# CTR_Connectors.net
KiCad netlist of a schematic drawn in Altium Designer
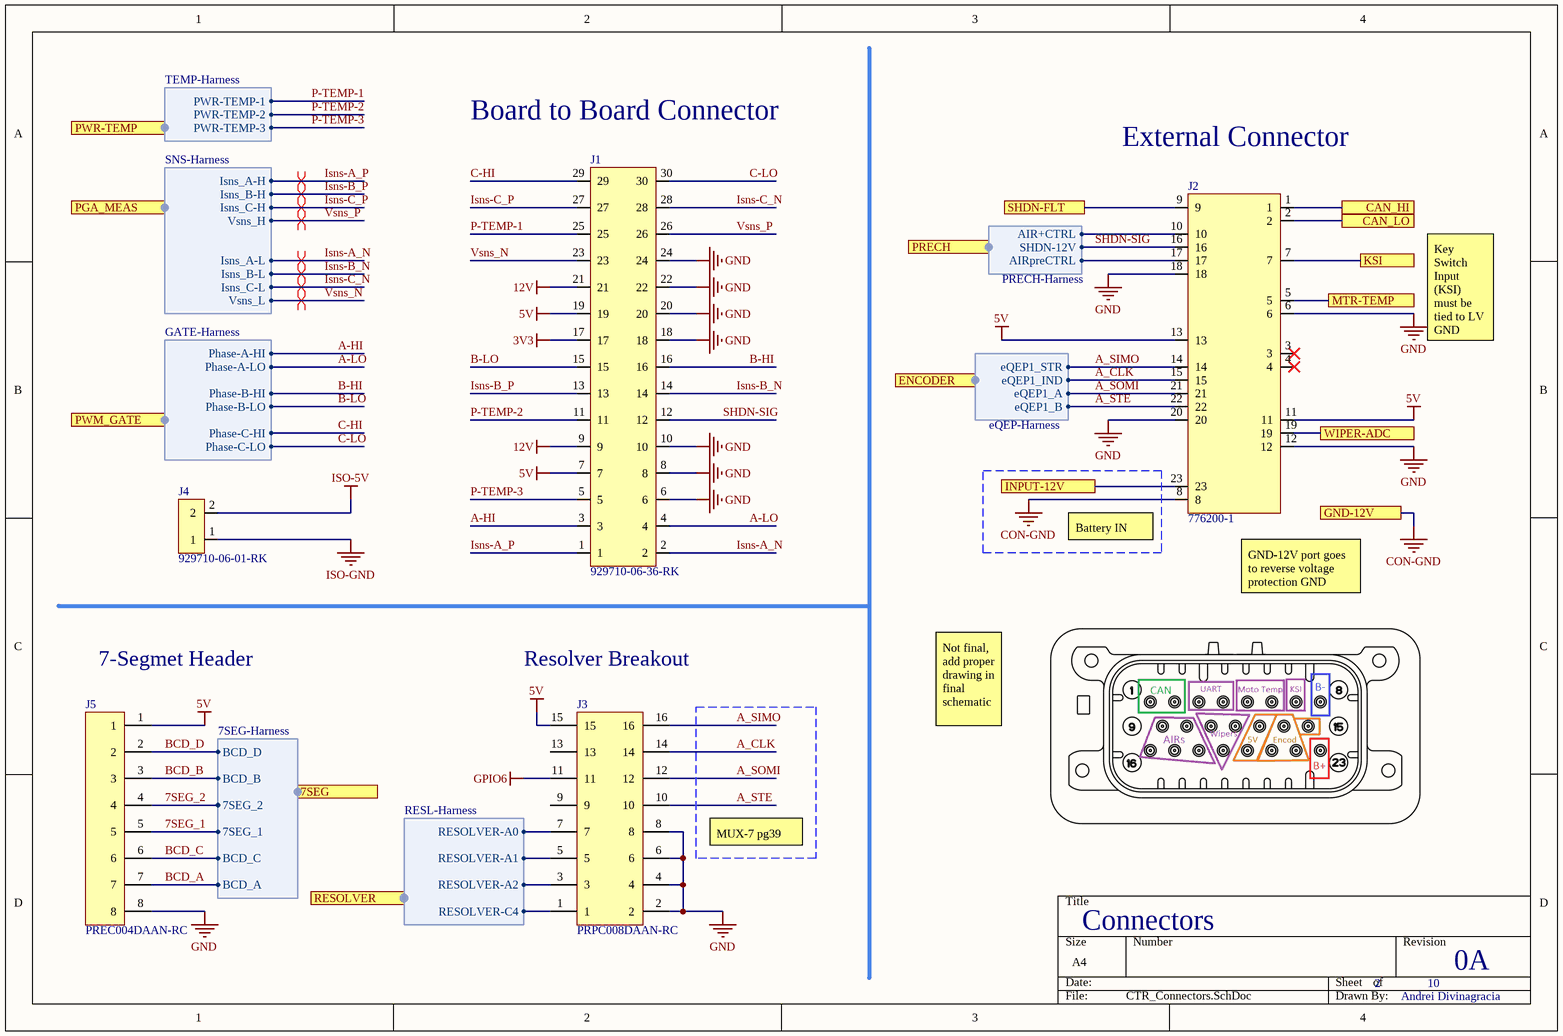
[diagram p0: CTR_Connectors.SchDoc]

(export (version "E")
  (design (tool "Eeschema 10.0.6"))
  (components
    (comp (ref "J1")
      (value "929710-06-36-RK")
      (footprint "CONN_30POS_M")
      (description "CONN HEADER VERT 72POS 2.54MM")
      (fields (field (name "MANUFACTURER") "3M"))
      (libsource (lib "InverterSCHLib") (part "CONN-72POS-M"))
    )
    (comp (ref "J2")
      (value "776200-1")
      (footprint "Conn 23POS")
      (description "CONN HEADER VERT 23POS 4MM")
      (fields (field (name "MANUFACTURER") "TE Connectivity AMP"))
      (libsource (lib "InverterSCHLib") (part "CONN-23POS"))
    )
    (comp (ref "J3")
      (value "PRPC008DAAN-RC")
      (footprint "16PIN_HEADER")
      (description "CONN HEADER VERT 16POS 2.54MM")
      (fields (field (name "MANUFACTURER") "Sullins"))
      (libsource (lib "InverterSCHLib") (part "PRPC008DAAN-RC"))
    )
    (comp (ref "J4")
      (value "929710-06-01-RK")
      (footprint "CONN-2POS-LONG-M")
      (description "CONN HEADER VERT 2POS")
      (fields (field (name "MANUFACTURER") "3M"))
      (libsource (lib "InverterSCHLib") (part "CONN-2POS-LONG-M"))
    )
    (comp (ref "J5")
      (value "PREC004DAAN-RC")
      (footprint "CONN-8PIN")
      (description "CONN HEADER VERT 8POS 2.54MM")
      (fields (field (name "MANUFACTURER") "Sullins"))
      (libsource (lib "InverterSCHLib") (part "CONN-8PIN"))
    )
  )
  (nets
    (net (code "8") (name "/7SEG_1") (class "Default")
      (node (ref "J5") (pin "5") (pinfunction "5_5") (pintype "passive"))
    )
    (net (code "9") (name "/7SEG_2") (class "Default")
      (node (ref "J5") (pin "4") (pinfunction "4_4") (pintype "passive"))
    )
    (net (code "11") (name "/A-HI") (class "Default")
      (node (ref "J1") (pin "3") (pinfunction "3_3") (pintype "passive"))
    )
    (net (code "12") (name "/A-LO") (class "Default")
      (node (ref "J1") (pin "4") (pinfunction "4_4") (pintype "passive"))
    )
    (net (code "13") (name "/AIR+CTRL") (class "Default")
      (node (ref "J2") (pin "10") (pinfunction "10_10") (pintype "passive"))
    )
    (net (code "14") (name "/AIRpreCTRL") (class "Default")
      (node (ref "J2") (pin "17") (pinfunction "17_17") (pintype "passive"))
    )
    (net (code "15") (name "/A_CLK") (class "Default")
      (node (ref "J2") (pin "15") (pinfunction "15_15") (pintype "passive"))
      (node (ref "J3") (pin "14") (pinfunction "14_14") (pintype "passive"))
    )
    (net (code "16") (name "/A_SIMO") (class "Default")
      (node (ref "J2") (pin "14") (pinfunction "14_14") (pintype "passive"))
      (node (ref "J3") (pin "16") (pinfunction "16_16") (pintype "passive"))
    )
    (net (code "17") (name "/A_SOMI") (class "Default")
      (node (ref "J2") (pin "21") (pinfunction "21_21") (pintype "passive"))
      (node (ref "J3") (pin "12") (pinfunction "12_12") (pintype "passive"))
    )
    (net (code "18") (name "/A_STE") (class "Default")
      (node (ref "J2") (pin "22") (pinfunction "22_22") (pintype "passive"))
      (node (ref "J3") (pin "10") (pinfunction "10_10") (pintype "passive"))
    )
    (net (code "19") (name "/B-HI") (class "Default")
      (node (ref "J1") (pin "16") (pinfunction "16_16") (pintype "passive"))
    )
    (net (code "20") (name "/B-LO") (class "Default")
      (node (ref "J1") (pin "15") (pinfunction "15_15") (pintype "passive"))
    )
    (net (code "21") (name "/BCD_A") (class "Default")
      (node (ref "J5") (pin "7") (pinfunction "7_7") (pintype "passive"))
    )
    (net (code "22") (name "/BCD_B") (class "Default")
      (node (ref "J5") (pin "3") (pinfunction "3_3") (pintype "passive"))
    )
    (net (code "23") (name "/BCD_C") (class "Default")
      (node (ref "J5") (pin "6") (pinfunction "6_6") (pintype "passive"))
    )
    (net (code "24") (name "/BCD_D") (class "Default")
      (node (ref "J5") (pin "2") (pinfunction "2_2") (pintype "passive"))
    )
    (net (code "25") (name "/C-HI") (class "Default")
      (node (ref "J1") (pin "29") (pinfunction "29_29") (pintype "passive"))
    )
    (net (code "26") (name "/C-LO") (class "Default")
      (node (ref "J1") (pin "30") (pinfunction "30_30") (pintype "passive"))
    )
    (net (code "27") (name "/CAN_HI") (class "Default")
      (node (ref "J2") (pin "1") (pinfunction "1_1") (pintype "passive"))
    )
    (net (code "28") (name "/CAN_LO") (class "Default")
      (node (ref "J2") (pin "2") (pinfunction "2_2") (pintype "passive"))
    )
    (net (code "29") (name "/INPUT-12V") (class "Default")
      (node (ref "J2") (pin "23") (pinfunction "23_23") (pintype "passive"))
    )
    (net (code "30") (name "/Isns-A_N") (class "Default")
      (node (ref "J1") (pin "2") (pinfunction "2_2") (pintype "passive"))
    )
    (net (code "31") (name "/Isns-A_P") (class "Default")
      (node (ref "J1") (pin "1") (pinfunction "1_1") (pintype "passive"))
    )
    (net (code "32") (name "/Isns-B_N") (class "Default")
      (node (ref "J1") (pin "14") (pinfunction "14_14") (pintype "passive"))
    )
    (net (code "33") (name "/Isns-B_P") (class "Default")
      (node (ref "J1") (pin "13") (pinfunction "13_13") (pintype "passive"))
    )
    (net (code "34") (name "/Isns-C_N") (class "Default")
      (node (ref "J1") (pin "28") (pinfunction "28_28") (pintype "passive"))
    )
    (net (code "35") (name "/Isns-C_P") (class "Default")
      (node (ref "J1") (pin "27") (pinfunction "27_27") (pintype "passive"))
    )
    (net (code "36") (name "/KSI") (class "Default")
      (node (ref "J2") (pin "7") (pinfunction "7_7") (pintype "passive"))
    )
    (net (code "37") (name "/MTR-TEMP") (class "Default")
      (node (ref "J2") (pin "5") (pinfunction "5_5") (pintype "passive"))
    )
    (net (code "38") (name "/P-TEMP-1") (class "Default")
      (node (ref "J1") (pin "25") (pinfunction "25_25") (pintype "passive"))
    )
    (net (code "39") (name "/P-TEMP-2") (class "Default")
      (node (ref "J1") (pin "11") (pinfunction "11_11") (pintype "passive"))
    )
    (net (code "40") (name "/P-TEMP-3") (class "Default")
      (node (ref "J1") (pin "5") (pinfunction "5_5") (pintype "passive"))
    )
    (net (code "41") (name "/RESOLVER-A0") (class "Default")
      (node (ref "J3") (pin "7") (pinfunction "7_7") (pintype "passive"))
    )
    (net (code "42") (name "/RESOLVER-A1") (class "Default")
      (node (ref "J3") (pin "5") (pinfunction "5_5") (pintype "passive"))
    )
    (net (code "43") (name "/RESOLVER-A2") (class "Default")
      (node (ref "J3") (pin "3") (pinfunction "3_3") (pintype "passive"))
    )
    (net (code "44") (name "/RESOLVER-C4") (class "Default")
      (node (ref "J3") (pin "1") (pinfunction "1_1") (pintype "passive"))
    )
    (net (code "45") (name "/SHDN-FLT") (class "Default")
      (node (ref "J2") (pin "9") (pinfunction "9_9") (pintype "passive"))
    )
    (net (code "46") (name "/SHDN-SIG") (class "Default")
      (node (ref "J1") (pin "12") (pinfunction "12_12") (pintype "passive"))
      (node (ref "J2") (pin "16") (pinfunction "16_16") (pintype "passive"))
    )
    (net (code "47") (name "/Vsns_N") (class "Default")
      (node (ref "J1") (pin "23") (pinfunction "23_23") (pintype "passive"))
    )
    (net (code "48") (name "/Vsns_P") (class "Default")
      (node (ref "J1") (pin "26") (pinfunction "26_26") (pintype "passive"))
    )
    (net (code "49") (name "/WIPER-ADC") (class "Default")
      (node (ref "J2") (pin "19") (pinfunction "19_19") (pintype "passive"))
    )
    (net (code "56") (name "3V3") (class "Default")
      (node (ref "J1") (pin "17") (pinfunction "17_17") (pintype "passive"))
    )
    (net (code "57") (name "5V") (class "Default")
      (node (ref "J1") (pin "19") (pinfunction "19_19") (pintype "passive"))
      (node (ref "J1") (pin "7") (pinfunction "7_7") (pintype "passive"))
      (node (ref "J2") (pin "11") (pinfunction "11_11") (pintype "passive"))
      (node (ref "J2") (pin "13") (pinfunction "13_13") (pintype "passive"))
      (node (ref "J3") (pin "15") (pinfunction "15_15") (pintype "passive"))
      (node (ref "J5") (pin "1") (pinfunction "1_1") (pintype "passive"))
    )
    (net (code "58") (name "12V") (class "Default")
      (node (ref "J1") (pin "21") (pinfunction "21_21") (pintype "passive"))
      (node (ref "J1") (pin "9") (pinfunction "9_9") (pintype "passive"))
    )
    (net (code "59") (name "CON-GND") (class "Default")
      (node (ref "J2") (pin "8") (pinfunction "8_8") (pintype "passive"))
    )
    (net (code "60") (name "GND") (class "Default")
      (node (ref "J1") (pin "10") (pinfunction "10_10") (pintype "passive"))
      (node (ref "J1") (pin "18") (pinfunction "18_18") (pintype "passive"))
      (node (ref "J1") (pin "20") (pinfunction "20_20") (pintype "passive"))
      (node (ref "J1") (pin "22") (pinfunction "22_22") (pintype "passive"))
      (node (ref "J1") (pin "24") (pinfunction "24_24") (pintype "passive"))
      (node (ref "J1") (pin "6") (pinfunction "6_6") (pintype "passive"))
      (node (ref "J1") (pin "8") (pinfunction "8_8") (pintype "passive"))
      (node (ref "J2") (pin "12") (pinfunction "12_12") (pintype "passive"))
      (node (ref "J2") (pin "18") (pinfunction "18_18") (pintype "passive"))
      (node (ref "J2") (pin "20") (pinfunction "20_20") (pintype "passive"))
      (node (ref "J2") (pin "6") (pinfunction "6_6") (pintype "passive"))
      (node (ref "J3") (pin "2") (pinfunction "2_2") (pintype "passive"))
      (node (ref "J3") (pin "4") (pinfunction "4_4") (pintype "passive"))
      (node (ref "J3") (pin "6") (pinfunction "6_6") (pintype "passive"))
      (node (ref "J3") (pin "8") (pinfunction "8_8") (pintype "passive"))
      (node (ref "J5") (pin "8") (pinfunction "8_8") (pintype "passive"))
    )
    (net (code "61") (name "GPIO6") (class "Default")
      (node (ref "J3") (pin "11") (pinfunction "11_11") (pintype "passive"))
    )
    (net (code "62") (name "ISO-5V") (class "Default")
      (node (ref "J4") (pin "2") (pinfunction "2_2") (pintype "passive"))
    )
    (net (code "63") (name "ISO-GND") (class "Default")
      (node (ref "J4") (pin "1") (pinfunction "1_1") (pintype "passive"))
    )
    (net (code "64") (name "unconnected-(J2-Pad3)") (class "Default")
      (node (ref "J2") (pin "3") (pinfunction "3_3") (pintype "passive+no_connect"))
    )
    (net (code "65") (name "unconnected-(J2-Pad4)") (class "Default")
      (node (ref "J2") (pin "4") (pinfunction "4_4") (pintype "passive+no_connect"))
    )
    (net (code "66") (name "unconnected-(J3-Pad9)") (class "Default")
      (node (ref "J3") (pin "9") (pinfunction "9_9") (pintype "passive"))
    )
    (net (code "67") (name "unconnected-(J3-Pad13)") (class "Default")
      (node (ref "J3") (pin "13") (pinfunction "13_13") (pintype "passive"))
    )
  )
)
